# Blinker_Board.net
KiCad netlist of a schematic drawn in EAGLE
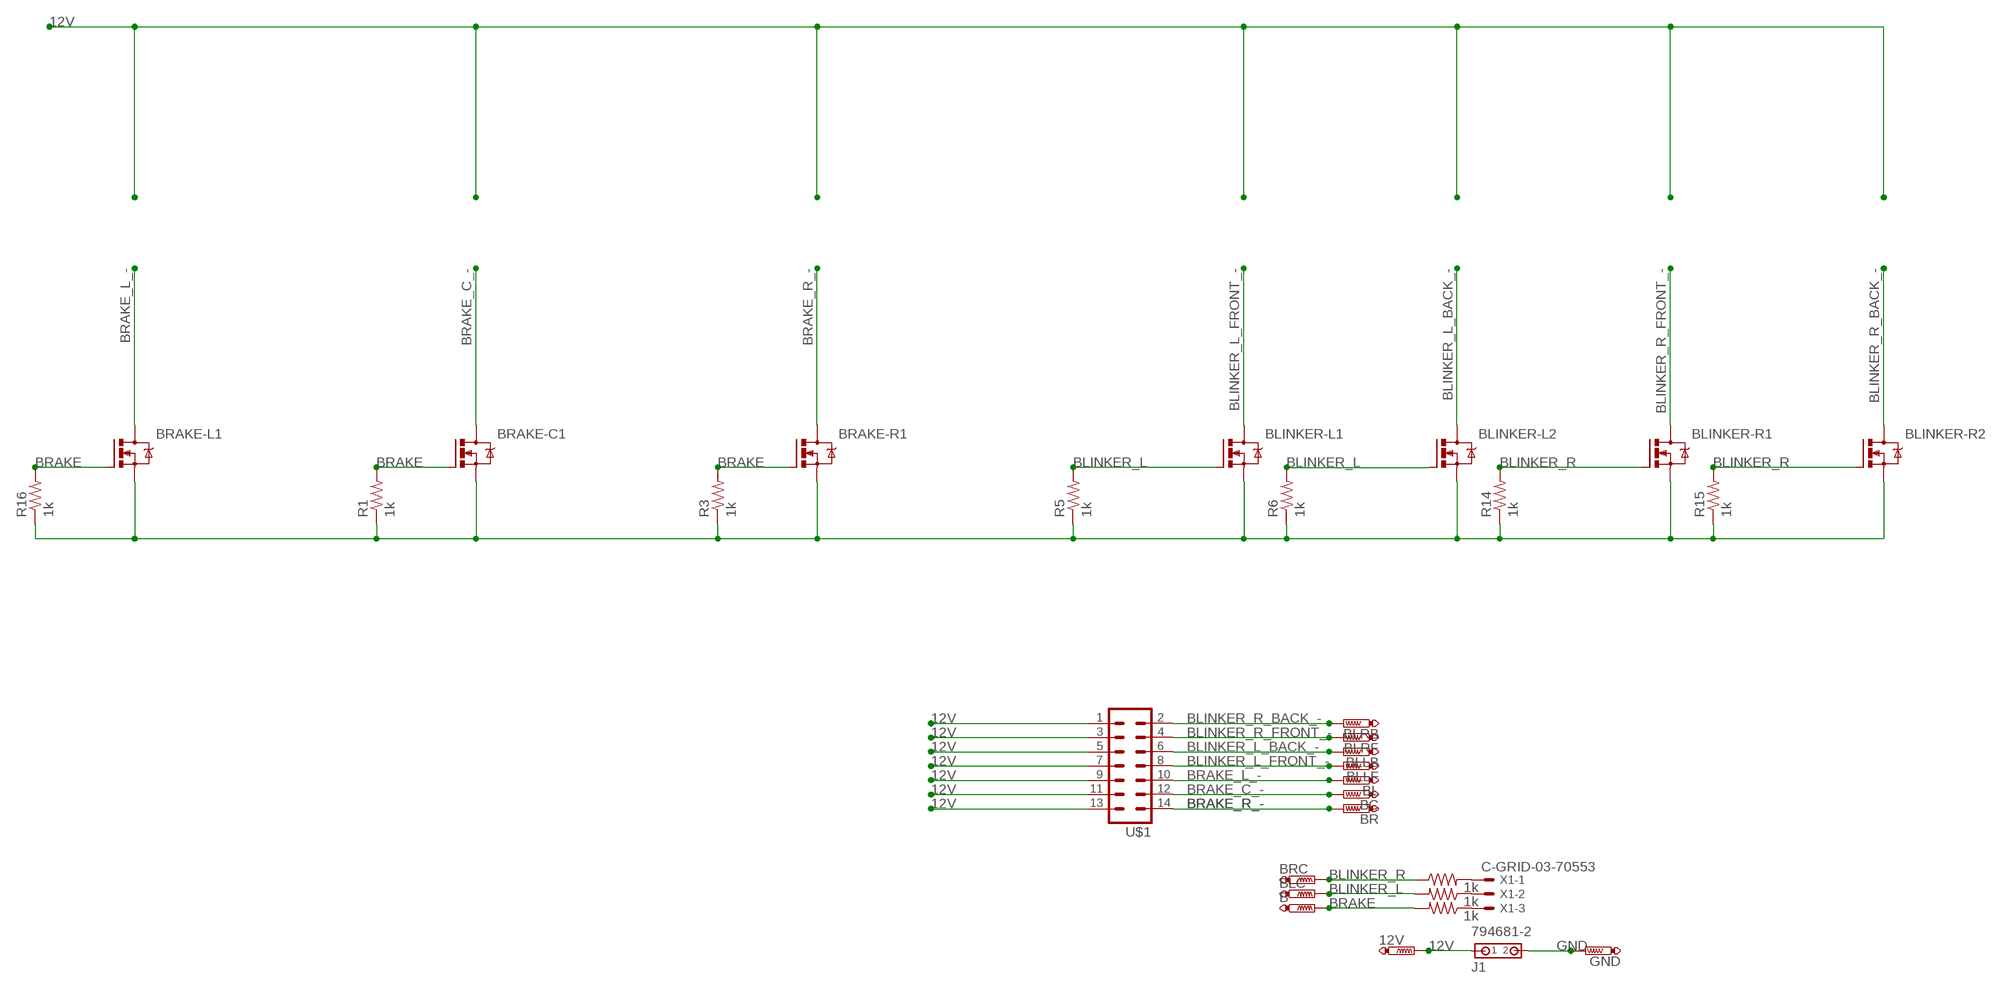
[diagram p0: schematic, sheet 1]

(export (version "E")
  (design (tool "Eeschema 10.0.6"))
  (components
    (comp (ref "12V")
      (value "TESTPAD-20MIL")
      (footprint "eagle-import:20MIL")
      (libsource (lib "eagle-import") (part "TESTPAD-20MIL"))
    )
    (comp (ref "B")
      (value "TESTPAD-20MIL")
      (footprint "eagle-import:20MIL")
      (libsource (lib "eagle-import") (part "TESTPAD-20MIL"))
    )
    (comp (ref "BC")
      (value "TESTPAD-20MIL")
      (footprint "eagle-import:20MIL")
      (libsource (lib "eagle-import") (part "TESTPAD-20MIL"))
    )
    (comp (ref "BL")
      (value "TESTPAD-20MIL")
      (footprint "eagle-import:20MIL")
      (libsource (lib "eagle-import") (part "TESTPAD-20MIL"))
    )
    (comp (ref "BLC")
      (value "TESTPAD-20MIL")
      (footprint "eagle-import:20MIL")
      (libsource (lib "eagle-import") (part "TESTPAD-20MIL"))
    )
    (comp (ref "BLINKER-L1")
      (value "PMV56XN215")
      (footprint "eagle-import:SOT23")
      (fields (field (name "PART_NUM") "PMV56XN,215"))
      (libsource (lib "eagle-import") (part "N-CHANNEL_MOSFETPMV56XN,215"))
    )
    (comp (ref "BLINKER-L2")
      (value "PMV56XN215")
      (footprint "eagle-import:SOT23")
      (fields (field (name "PART_NUM") "PMV56XN,215"))
      (libsource (lib "eagle-import") (part "N-CHANNEL_MOSFETPMV56XN,215"))
    )
    (comp (ref "BLINKER-R1")
      (value "PMV56XN215")
      (footprint "eagle-import:SOT23")
      (fields (field (name "PART_NUM") "PMV56XN,215"))
      (libsource (lib "eagle-import") (part "N-CHANNEL_MOSFETPMV56XN,215"))
    )
    (comp (ref "BLINKER-R2")
      (value "PMV56XN215")
      (footprint "eagle-import:SOT23")
      (fields (field (name "PART_NUM") "PMV56XN,215"))
      (libsource (lib "eagle-import") (part "N-CHANNEL_MOSFETPMV56XN,215"))
    )
    (comp (ref "BLLB")
      (value "TESTPAD-20MIL")
      (footprint "eagle-import:20MIL")
      (libsource (lib "eagle-import") (part "TESTPAD-20MIL"))
    )
    (comp (ref "BLLF")
      (value "TESTPAD-20MIL")
      (footprint "eagle-import:20MIL")
      (libsource (lib "eagle-import") (part "TESTPAD-20MIL"))
    )
    (comp (ref "BLRB")
      (value "TESTPAD-20MIL")
      (footprint "eagle-import:20MIL")
      (libsource (lib "eagle-import") (part "TESTPAD-20MIL"))
    )
    (comp (ref "BLRF")
      (value "TESTPAD-20MIL")
      (footprint "eagle-import:20MIL")
      (libsource (lib "eagle-import") (part "TESTPAD-20MIL"))
    )
    (comp (ref "BR")
      (value "TESTPAD-20MIL")
      (footprint "eagle-import:20MIL")
      (libsource (lib "eagle-import") (part "TESTPAD-20MIL"))
    )
    (comp (ref "BRAKE-C1")
      (value "N-CHANNEL_MOSFETPMV56XN,215")
      (footprint "eagle-import:SOT23")
      (fields (field (name "PART_NUM") "PMV56XN,215") (field (name "PART_NUM_1") "PMV56XN,215"))
      (libsource (lib "eagle-import") (part "N-CHANNEL_MOSFETPMV56XN,215"))
    )
    (comp (ref "BRAKE-L1")
      (value "PMV56XN215")
      (footprint "eagle-import:SOT23")
      (fields (field (name "PART_NUM") "PMV56XN,215") (field (name "PART_NUM_1") "PMV56XN,215"))
      (libsource (lib "eagle-import") (part "N-CHANNEL_MOSFETPMV56XN,215"))
    )
    (comp (ref "BRAKE-R1")
      (value "PMV56XN215")
      (footprint "eagle-import:SOT23")
      (fields (field (name "PART_NUM") "PMV56XN,215"))
      (libsource (lib "eagle-import") (part "N-CHANNEL_MOSFETPMV56XN,215"))
    )
    (comp (ref "BRC")
      (value "TESTPAD-20MIL")
      (footprint "eagle-import:20MIL")
      (libsource (lib "eagle-import") (part "TESTPAD-20MIL"))
    )
    (comp (ref "GND")
      (value "TESTPAD-20MIL")
      (footprint "eagle-import:20MIL")
      (libsource (lib "eagle-import") (part "TESTPAD-20MIL"))
    )
    (comp (ref "J1")
      (value "794681-2")
      (footprint "eagle-import:794681-2")
      (libsource (lib "eagle-import") (part "794681-2"))
    )
    (comp (ref "R1")
      (value "1k")
      (footprint "eagle-import:R1206")
      (fields (field (name "PART_NUM") "CR1206-FX-1001GLF"))
      (libsource (lib "eagle-import") (part "RESISTORSMD1206"))
    )
    (comp (ref "R3")
      (value "1k")
      (footprint "eagle-import:R1206")
      (fields (field (name "PART_NUM") "CR1206-FX-1001GLF"))
      (libsource (lib "eagle-import") (part "RESISTORSMD1206"))
    )
    (comp (ref "R5")
      (value "1k")
      (footprint "eagle-import:R1206")
      (fields (field (name "PART_NUM") "CR1206-FX-1001GLF"))
      (libsource (lib "eagle-import") (part "RESISTORSMD1206"))
    )
    (comp (ref "R6")
      (value "1k")
      (footprint "eagle-import:R1206")
      (fields (field (name "PART_NUM") "CR1206-FX-1001GLF"))
      (libsource (lib "eagle-import") (part "RESISTORSMD1206"))
    )
    (comp (ref "R7")
      (value "1k")
      (footprint "eagle-import:R1206")
      (fields (field (name "PART_NUM") "CR1206-FX-1001GLF"))
      (libsource (lib "eagle-import") (part "RESISTORSMD1206"))
    )
    (comp (ref "R9")
      (value "1k")
      (footprint "eagle-import:R1206")
      (fields (field (name "PART_NUM") "CR1206-FX-1001GLF"))
      (libsource (lib "eagle-import") (part "RESISTORSMD1206"))
    )
    (comp (ref "R10")
      (value "1k")
      (footprint "eagle-import:R1206")
      (fields (field (name "PART_NUM") "CR1206-FX-1001GLF"))
      (libsource (lib "eagle-import") (part "RESISTORSMD1206"))
    )
    (comp (ref "R14")
      (value "1k")
      (footprint "eagle-import:R1206")
      (fields (field (name "PART_NUM") "CR1206-FX-1001GLF"))
      (libsource (lib "eagle-import") (part "RESISTORSMD1206"))
    )
    (comp (ref "R15")
      (value "1k")
      (footprint "eagle-import:R1206")
      (fields (field (name "PART_NUM") "CR1206-FX-1001GLF"))
      (libsource (lib "eagle-import") (part "RESISTORSMD1206"))
    )
    (comp (ref "R16")
      (value "1k")
      (footprint "eagle-import:R1206")
      (fields (field (name "PART_NUM") "CR1206-FX-1001GLF"))
      (libsource (lib "eagle-import") (part "RESISTORSMD1206"))
    )
    (comp (ref "U$1")
      (value "AMP_LATCH_14")
      (footprint "eagle-import:MA14-2")
      (libsource (lib "eagle-import") (part "AMP_LATCH_14"))
    )
    (comp (ref "X1")
      (value "C-GRID-03-70553")
      (footprint "eagle-import:70553-03")
      (libsource (lib "eagle-import") (part "C-GRID-03-70553"))
    )
  )
  (nets
    (net (code "1") (name "/12V") (class "Default")
      (node (ref "12V") (pin "P$1") (pinfunction "TP_P$1") (pintype "input"))
      (node (ref "J1") (pin "1") (pinfunction "1_1") (pintype "passive"))
      (node (ref "U$1") (pin "1") (pinfunction "7_1") (pintype "passive"))
      (node (ref "U$1") (pin "11") (pinfunction "17_11") (pintype "passive"))
      (node (ref "U$1") (pin "13") (pinfunction "19_13") (pintype "passive"))
      (node (ref "U$1") (pin "3") (pinfunction "9_3") (pintype "passive"))
      (node (ref "U$1") (pin "5") (pinfunction "11_5") (pintype "passive"))
      (node (ref "U$1") (pin "7") (pinfunction "13_7") (pintype "passive"))
      (node (ref "U$1") (pin "9") (pinfunction "15_9") (pintype "passive"))
    )
    (net (code "2") (name "/BLINKER_L") (class "Default")
      (node (ref "BLC") (pin "P$1") (pinfunction "TP_P$1") (pintype "input"))
      (node (ref "BLINKER-L1") (pin "1") (pinfunction "G_1") (pintype "passive"))
      (node (ref "BLINKER-L2") (pin "1") (pinfunction "G_1") (pintype "passive"))
      (node (ref "R10") (pin "2") (pinfunction "2_2") (pintype "passive"))
      (node (ref "R5") (pin "2") (pinfunction "2_2") (pintype "passive"))
      (node (ref "R6") (pin "2") (pinfunction "2_2") (pintype "passive"))
    )
    (net (code "3") (name "/BLINKER_L_BACK_-") (class "Default")
      (node (ref "BLINKER-L2") (pin "3") (pinfunction "D_3") (pintype "passive"))
      (node (ref "BLLB") (pin "P$1") (pinfunction "TP_P$1") (pintype "input"))
      (node (ref "U$1") (pin "6") (pinfunction "12_6") (pintype "passive"))
    )
    (net (code "4") (name "/BLINKER_L_FRONT_-") (class "Default")
      (node (ref "BLINKER-L1") (pin "3") (pinfunction "D_3") (pintype "passive"))
      (node (ref "BLLF") (pin "P$1") (pinfunction "TP_P$1") (pintype "input"))
      (node (ref "U$1") (pin "8") (pinfunction "14_8") (pintype "passive"))
    )
    (net (code "5") (name "/BLINKER_R") (class "Default")
      (node (ref "BLINKER-R1") (pin "1") (pinfunction "G_1") (pintype "passive"))
      (node (ref "BLINKER-R2") (pin "1") (pinfunction "G_1") (pintype "passive"))
      (node (ref "BRC") (pin "P$1") (pinfunction "TP_P$1") (pintype "input"))
      (node (ref "R14") (pin "2") (pinfunction "2_2") (pintype "passive"))
      (node (ref "R15") (pin "2") (pinfunction "2_2") (pintype "passive"))
      (node (ref "R7") (pin "1") (pinfunction "1_1") (pintype "passive"))
    )
    (net (code "6") (name "/BLINKER_R_BACK_-") (class "Default")
      (node (ref "BLINKER-R2") (pin "3") (pinfunction "D_3") (pintype "passive"))
      (node (ref "BLRB") (pin "P$1") (pinfunction "TP_P$1") (pintype "input"))
      (node (ref "U$1") (pin "2") (pinfunction "8_2") (pintype "passive"))
    )
    (net (code "7") (name "/BLINKER_R_FRONT_-") (class "Default")
      (node (ref "BLINKER-R1") (pin "3") (pinfunction "D_3") (pintype "passive"))
      (node (ref "BLRF") (pin "P$1") (pinfunction "TP_P$1") (pintype "input"))
      (node (ref "U$1") (pin "4") (pinfunction "10_4") (pintype "passive"))
    )
    (net (code "8") (name "/BRAKE") (class "Default")
      (node (ref "B") (pin "P$1") (pinfunction "TP_P$1") (pintype "input"))
      (node (ref "BRAKE-C1") (pin "1") (pinfunction "G_1") (pintype "passive"))
      (node (ref "BRAKE-L1") (pin "1") (pinfunction "G_1") (pintype "passive"))
      (node (ref "BRAKE-R1") (pin "1") (pinfunction "G_1") (pintype "passive"))
      (node (ref "R1") (pin "2") (pinfunction "2_2") (pintype "passive"))
      (node (ref "R16") (pin "2") (pinfunction "2_2") (pintype "passive"))
      (node (ref "R3") (pin "2") (pinfunction "2_2") (pintype "passive"))
      (node (ref "R9") (pin "2") (pinfunction "2_2") (pintype "passive"))
    )
    (net (code "9") (name "/BRAKE_C_-") (class "Default")
      (node (ref "BC") (pin "P$1") (pinfunction "TP_P$1") (pintype "input"))
      (node (ref "BRAKE-C1") (pin "3") (pinfunction "D_3") (pintype "passive"))
      (node (ref "U$1") (pin "12") (pinfunction "18_12") (pintype "passive"))
    )
    (net (code "10") (name "/BRAKE_L_-") (class "Default")
      (node (ref "BL") (pin "P$1") (pinfunction "TP_P$1") (pintype "input"))
      (node (ref "BRAKE-L1") (pin "3") (pinfunction "D_3") (pintype "passive"))
      (node (ref "U$1") (pin "10") (pinfunction "16_10") (pintype "passive"))
    )
    (net (code "11") (name "/BRAKE_R_-") (class "Default")
      (node (ref "BR") (pin "P$1") (pinfunction "TP_P$1") (pintype "input"))
      (node (ref "BRAKE-R1") (pin "3") (pinfunction "D_3") (pintype "passive"))
      (node (ref "U$1") (pin "14") (pinfunction "20_14") (pintype "passive"))
    )
    (net (code "12") (name "/GND") (class "Default")
      (node (ref "BLINKER-L1") (pin "2") (pinfunction "S_2") (pintype "passive"))
      (node (ref "BLINKER-L2") (pin "2") (pinfunction "S_2") (pintype "passive"))
      (node (ref "BLINKER-R1") (pin "2") (pinfunction "S_2") (pintype "passive"))
      (node (ref "BLINKER-R2") (pin "2") (pinfunction "S_2") (pintype "passive"))
      (node (ref "BRAKE-C1") (pin "2") (pinfunction "S_2") (pintype "passive"))
      (node (ref "BRAKE-L1") (pin "2") (pinfunction "S_2") (pintype "passive"))
      (node (ref "BRAKE-R1") (pin "2") (pinfunction "S_2") (pintype "passive"))
      (node (ref "GND") (pin "P$1") (pinfunction "TP_P$1") (pintype "input"))
      (node (ref "J1") (pin "2") (pinfunction "2_2") (pintype "passive"))
      (node (ref "R1") (pin "1") (pinfunction "1_1") (pintype "passive"))
      (node (ref "R14") (pin "1") (pinfunction "1_1") (pintype "passive"))
      (node (ref "R15") (pin "1") (pinfunction "1_1") (pintype "passive"))
      (node (ref "R16") (pin "1") (pinfunction "1_1") (pintype "passive"))
      (node (ref "R3") (pin "1") (pinfunction "1_1") (pintype "passive"))
      (node (ref "R5") (pin "1") (pinfunction "1_1") (pintype "passive"))
      (node (ref "R6") (pin "1") (pinfunction "1_1") (pintype "passive"))
    )
    (net (code "13") (name "Net-(X1A-S)") (class "Default")
      (node (ref "R7") (pin "2") (pinfunction "2_2") (pintype "passive"))
      (node (ref "X1") (pin "1") (pinfunction "S_1") (pintype "passive"))
    )
    (net (code "14") (name "Net-(X1B-S)") (class "Default")
      (node (ref "R10") (pin "1") (pinfunction "1_1") (pintype "passive"))
      (node (ref "X1") (pin "2") (pinfunction "S_2") (pintype "passive"))
    )
    (net (code "15") (name "Net-(X1C-S)") (class "Default")
      (node (ref "R9") (pin "1") (pinfunction "1_1") (pintype "passive"))
      (node (ref "X1") (pin "3") (pinfunction "S_3") (pintype "passive"))
    )
  )
)
